# CoinCellBreakOut.net
KiCad netlist of a schematic drawn in EAGLE
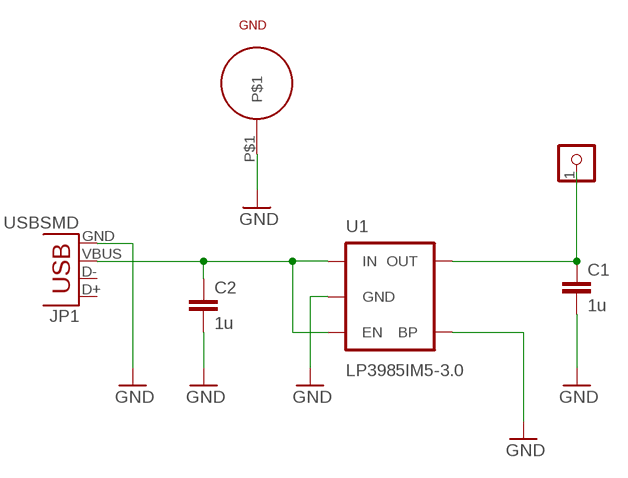
[diagram p0: schematic, sheet 1]

(export (version "E")
  (design (tool "Eeschema 10.0.6"))
  (components
    (comp (ref "3V")
      (value "CON_HEADER_1X01-PTH_10_17")
      (footprint "eagle-import:M1X2_10_17")
      (libsource (lib "eagle-import") (part "CON_HEADER_1X01-PTH_10_17"))
    )
    (comp (ref "C1")
      (value "1u")
      (footprint "eagle-import:0603-CAP")
      (libsource (lib "eagle-import") (part "CAP0603-CAP"))
    )
    (comp (ref "C2")
      (value "1u")
      (footprint "eagle-import:0603-CAP")
      (libsource (lib "eagle-import") (part "CAP0603-CAP"))
    )
    (comp (ref "GND")
      (value "COIN_CELL_CONTACT")
      (footprint "eagle-import:COIN_CELL_CONTACT")
      (libsource (lib "eagle-import") (part "COIN_CELL_CONTACT"))
    )
    (comp (ref "JP1")
      (value "USBSMD")
      (footprint "eagle-import:USB-MINIB")
      (libsource (lib "eagle-import") (part "USBSMD"))
    )
    (comp (ref "U1")
      (value "LP3985IM5-3.0")
      (footprint "eagle-import:SOT23-5")
      (libsource (lib "eagle-import") (part "V_REG_LDOSMD"))
    )
  )
  (nets
    (net (code "1") (name "GND") (class "Default")
      (node (ref "C1") (pin "2") (pinfunction "2_2") (pintype "passive"))
      (node (ref "C2") (pin "2") (pinfunction "2_2") (pintype "passive"))
      (node (ref "GND") (pin "P$1") (pinfunction "P$1_P$1") (pintype "bidirectional"))
      (node (ref "JP1") (pin "GND") (pinfunction "GND_GND") (pintype "bidirectional"))
      (node (ref "U1") (pin "2") (pinfunction "GND_2") (pintype "input"))
      (node (ref "U1") (pin "4") (pinfunction "BP_4") (pintype "input"))
    )
    (net (code "2") (name "Net-(U1-EN)") (class "Default")
      (node (ref "C2") (pin "1") (pinfunction "1_1") (pintype "passive"))
      (node (ref "JP1") (pin "VBUS") (pinfunction "VBUS_VBUS") (pintype "bidirectional"))
      (node (ref "U1") (pin "1") (pinfunction "IN_1") (pintype "input"))
      (node (ref "U1") (pin "3") (pinfunction "EN_3") (pintype "input"))
    )
    (net (code "3") (name "Net-(U1-OUT)") (class "Default")
      (node (ref "3V") (pin "1") (pinfunction "1_1") (pintype "passive"))
      (node (ref "C1") (pin "1") (pinfunction "1_1") (pintype "passive"))
      (node (ref "U1") (pin "5") (pinfunction "OUT_5") (pintype "passive"))
    )
    (net (code "4") (name "unconnected-(JP1-PadD+)") (class "Default")
      (node (ref "JP1") (pin "D+") (pinfunction "D+_D+") (pintype "bidirectional"))
    )
    (net (code "5") (name "unconnected-(JP1-PadD-)") (class "Default")
      (node (ref "JP1") (pin "D-") (pinfunction "D-_D-") (pintype "bidirectional"))
    )
  )
)
